# Sensors.net
KiCad netlist of a schematic drawn in Altium Designer
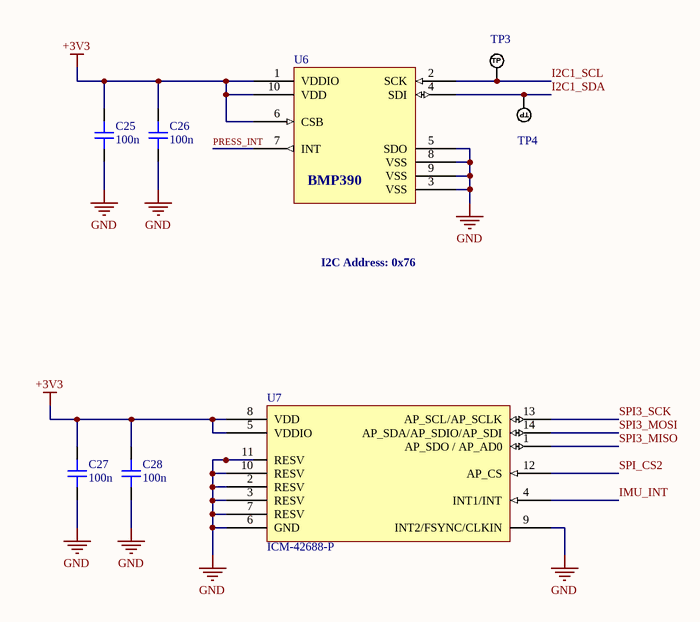
[diagram p0: Sensors.SchDoc]

(export (version "E")
  (design (tool "Eeschema 10.0.6"))
  (components
    (comp (ref "C25")
      (value "100n")
      (footprint "CAP_0402")
      (description "Capacitor SMD 0402")
      (libsource (lib "Schematic-Lib-PhilsLab") (part "CAP_0402"))
    )
    (comp (ref "C26")
      (value "100n")
      (footprint "CAP_0402")
      (description "Capacitor SMD 0402")
      (libsource (lib "Schematic-Lib-PhilsLab") (part "CAP_0402"))
    )
    (comp (ref "C27")
      (value "100n")
      (footprint "CAP_0402")
      (description "Capacitor SMD 0402")
      (libsource (lib "Schematic-Lib-PhilsLab") (part "CAP_0402"))
    )
    (comp (ref "C28")
      (value "100n")
      (footprint "CAP_0402")
      (description "Capacitor SMD 0402")
      (libsource (lib "Schematic-Lib-PhilsLab") (part "CAP_0402"))
    )
    (comp (ref "TP3")
      (value "TP_NOBOM")
      (footprint "PAD_RND_1MM")
      (description "Test Point Round 1mm (NO BOM)")
      (libsource (lib "Schematic-Lib-PhilsLab") (part "TEST_POINT_RND_1MM"))
    )
    (comp (ref "TP4")
      (value "TP_NOBOM")
      (footprint "PAD_RND_1MM")
      (description "Test Point Round 1mm (NO BOM)")
      (libsource (lib "Schematic-Lib-PhilsLab") (part "TEST_POINT_RND_1MM"))
    )
    (comp (ref "U6")
      (value "BMP390")
      (footprint "LGA 10-pin ball")
      (description "Pressure Sensor 4.35 ~ 18.13PSI (30 ~ 125kPa) Absolute 10-WFLGA")
      (libsource (lib "AltiumSchLib") (part "BMP390"))
    )
    (comp (ref "U7")
      (value "ICM-42688-P")
      (footprint "14 Lead LGA")
      (description "High Precision 6-Axis MEMS MotionTrackingTM Device")
      (libsource (lib "AltiumSchLib") (part "ICM-42688-P"))
    )
  )
  (nets
    (net (code "1") (name "+3V3") (class "Default")
      (node (ref "C25") (pin "2") (pinfunction "2_2") (pintype "passive"))
      (node (ref "C26") (pin "2") (pinfunction "2_2") (pintype "passive"))
      (node (ref "C27") (pin "2") (pinfunction "2_2") (pintype "passive"))
      (node (ref "C28") (pin "2") (pinfunction "2_2") (pintype "passive"))
      (node (ref "U6") (pin "1") (pinfunction "VDDIO_1") (pintype "power_in"))
      (node (ref "U6") (pin "10") (pinfunction "VDD_10") (pintype "power_in"))
      (node (ref "U6") (pin "6") (pinfunction "CSB_6") (pintype "input"))
      (node (ref "U7") (pin "5") (pinfunction "VDDIO_5") (pintype "power_in"))
      (node (ref "U7") (pin "8") (pinfunction "VDD_8") (pintype "power_in"))
    )
    (net (code "2") (name "/I2C1_SCL") (class "Default")
      (node (ref "TP3") (pin "1") (pinfunction "TP_1") (pintype "passive"))
      (node (ref "U6") (pin "2") (pinfunction "SCK_2") (pintype "input"))
    )
    (net (code "3") (name "/I2C1_SDA") (class "Default")
      (node (ref "TP4") (pin "1") (pinfunction "TP_1") (pintype "passive"))
      (node (ref "U6") (pin "4") (pinfunction "SDI_4") (pintype "bidirectional"))
    )
    (net (code "4") (name "/IMU_INT") (class "Default")
      (node (ref "U7") (pin "4") (pinfunction "INT1/INT_4") (pintype "input"))
    )
    (net (code "5") (name "/PRESS_INT") (class "Default")
      (node (ref "U6") (pin "7") (pinfunction "INT_7") (pintype "output"))
    )
    (net (code "6") (name "/SPI3_MISO") (class "Default")
      (node (ref "U7") (pin "1") (pinfunction "AP_SDO_/_AP_AD0_1") (pintype "bidirectional"))
    )
    (net (code "7") (name "/SPI3_MOSI") (class "Default")
      (node (ref "U7") (pin "14") (pinfunction "AP_SDA/AP_SDIO/AP_SDI_14") (pintype "bidirectional"))
    )
    (net (code "8") (name "/SPI3_SCK") (class "Default")
      (node (ref "U7") (pin "13") (pinfunction "AP_SCL/AP_SCLK_13") (pintype "bidirectional"))
    )
    (net (code "9") (name "/SPI_CS2") (class "Default")
      (node (ref "U7") (pin "12") (pinfunction "AP_CS_12") (pintype "input"))
    )
    (net (code "10") (name "GND") (class "Default")
      (node (ref "C25") (pin "1") (pinfunction "1_1") (pintype "passive"))
      (node (ref "C26") (pin "1") (pinfunction "1_1") (pintype "passive"))
      (node (ref "C27") (pin "1") (pinfunction "1_1") (pintype "passive"))
      (node (ref "C28") (pin "1") (pinfunction "1_1") (pintype "passive"))
      (node (ref "U6") (pin "3") (pinfunction "VSS_3") (pintype "power_in"))
      (node (ref "U6") (pin "5") (pinfunction "SDO_5") (pintype "power_in"))
      (node (ref "U6") (pin "8") (pinfunction "VSS_8") (pintype "power_in"))
      (node (ref "U6") (pin "9") (pinfunction "VSS_9") (pintype "power_in"))
      (node (ref "U7") (pin "10") (pinfunction "RESV_10") (pintype "power_in"))
      (node (ref "U7") (pin "11") (pinfunction "RESV_11") (pintype "power_in"))
      (node (ref "U7") (pin "2") (pinfunction "RESV_2") (pintype "power_in"))
      (node (ref "U7") (pin "3") (pinfunction "RESV_3") (pintype "power_in"))
      (node (ref "U7") (pin "6") (pinfunction "GND_6") (pintype "power_in"))
      (node (ref "U7") (pin "7") (pinfunction "RESV_7") (pintype "power_in"))
      (node (ref "U7") (pin "9") (pinfunction "INT2/FSYNC/CLKIN_9") (pintype "power_in"))
    )
  )
)
